# mini_pcie.net
KiCad netlist of a schematic drawn in Altium Designer
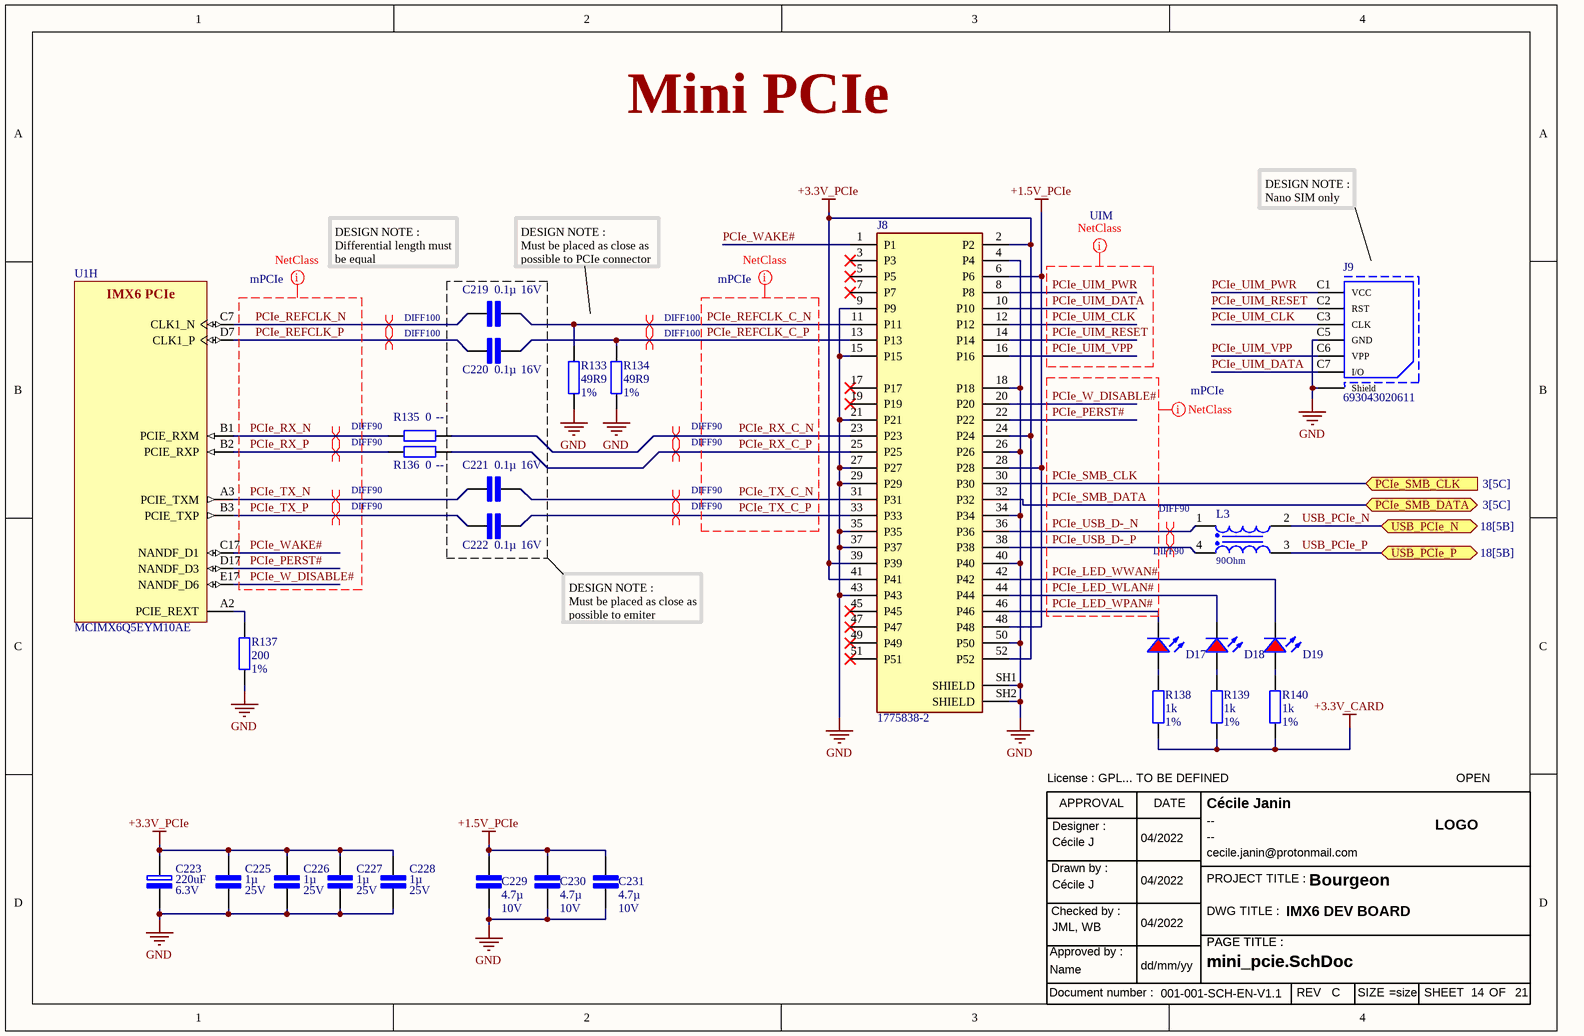
[diagram p0: mini_pcie.SchDoc]

(export (version "E")
  (design (tool "Eeschema 10.0.6"))
  (components
    (comp (ref "C219")
      (value "0.1µ")
      (footprint "Cap cer 0402/1005")
      (description "cap solid electrolyte 0.1µ 6.3V 10%")
      (fields (field (name "TENSION DU DIÉLECTRIQUE") "16V"))
      (libsource (lib "First Board IMX6") (part "cap 0.1µ 16V"))
    )
    (comp (ref "C220")
      (value "0.1µ")
      (footprint "Cap cer 0402/1005")
      (description "cap solid electrolyte 0.1µ 6.3V 10%")
      (fields (field (name "TENSION DU DIÉLECTRIQUE") "16V"))
      (libsource (lib "First Board IMX6") (part "cap 0.1µ 16V"))
    )
    (comp (ref "C221")
      (value "0.1µ")
      (footprint "Cap cer 0402/1005")
      (description "cap solid electrolyte 0.1µ 6.3V 10%")
      (fields (field (name "TENSION DU DIÉLECTRIQUE") "16V"))
      (libsource (lib "First Board IMX6") (part "cap 0.1µ 16V"))
    )
    (comp (ref "C222")
      (value "0.1µ")
      (footprint "Cap cer 0402/1005")
      (description "cap solid electrolyte 0.1µ 6.3V 10%")
      (fields (field (name "TENSION DU DIÉLECTRIQUE") "16V"))
      (libsource (lib "First Board IMX6") (part "cap 0.1µ 16V"))
    )
    (comp (ref "C223")
      (value "220uF")
      (footprint "cap polymer wurth")
      (description "WCAP-PHGP Aluminum Polymer Capacitor, H-Chip SMT, L7.3W4.3H1.9mm, 220uF, 6.3V 875015119006")
      (fields
        (field (name "MANUFACTURER") "Wurth Elektronik")
        (field (name "MANUFACTURER PART NUMBER") "875015119006")
        (field (name "RATED VOLTAGE (DC)") "6.3V")
      )
      (libsource (lib "First Board IMX6") (part "cap 220µ 6.3V"))
    )
    (comp (ref "C225")
      (value "1µ")
      (footprint "Cap cer 0402/1005")
      (description "cap cer 1µ 25V 10% X5R 0402")
      (fields (field (name "TENSION DU DIÉLECTRIQUE") "25V"))
      (libsource (lib "First Board IMX6") (part "cap 1µ 25V"))
    )
    (comp (ref "C226")
      (value "1µ")
      (footprint "Cap cer 0402/1005")
      (description "cap cer 1µ 25V 10% X5R 0402")
      (fields (field (name "TENSION DU DIÉLECTRIQUE") "25V"))
      (libsource (lib "First Board IMX6") (part "cap 1µ 25V"))
    )
    (comp (ref "C227")
      (value "1µ")
      (footprint "Cap cer 0402/1005")
      (description "cap cer 1µ 25V 10% X5R 0402")
      (fields (field (name "TENSION DU DIÉLECTRIQUE") "25V"))
      (libsource (lib "First Board IMX6") (part "cap 1µ 25V"))
    )
    (comp (ref "C228")
      (value "1µ")
      (footprint "Cap cer 0402/1005")
      (description "cap cer 1µ 25V 10% X5R 0402")
      (fields (field (name "TENSION DU DIÉLECTRIQUE") "25V"))
      (libsource (lib "First Board IMX6") (part "cap 1µ 25V"))
    )
    (comp (ref "C229")
      (value "4.7µ")
      (footprint "Cap cer 0402/1005")
      (description "cap cer 4.7µ 10V 10% X7R 0402")
      (fields (field (name "TENSION DU DIÉLECTRIQUE") "10V"))
      (libsource (lib "First Board IMX6") (part "cap 4.7µ 10V"))
    )
    (comp (ref "C230")
      (value "4.7µ")
      (footprint "Cap cer 0402/1005")
      (description "cap cer 4.7µ 10V 10% X7R 0402")
      (fields (field (name "TENSION DU DIÉLECTRIQUE") "10V"))
      (libsource (lib "First Board IMX6") (part "cap 4.7µ 10V"))
    )
    (comp (ref "C231")
      (value "4.7µ")
      (footprint "Cap cer 0402/1005")
      (description "cap cer 4.7µ 10V 10% X7R 0402")
      (fields (field (name "TENSION DU DIÉLECTRIQUE") "10V"))
      (libsource (lib "First Board IMX6") (part "cap 4.7µ 10V"))
    )
    (comp (ref "D17")
      (value "Red, 2V, 120deg")
      (footprint "LED red 0603")
      (description "WL-SMCC SMD Mono-color Chip LED Compact, size 0603, Red, 2V, 120deg 150060RS73220")
      (fields (field (name "PART NUMBER") "150060RS73220") (field (name "PUBLISHER") "Wurth Elektronik"))
      (libsource (lib "First Board IMX6") (part "LED Red 0603"))
    )
    (comp (ref "D18")
      (value "Red, 2V, 120deg")
      (footprint "LED red 0603")
      (description "WL-SMCC SMD Mono-color Chip LED Compact, size 0603, Red, 2V, 120deg 150060RS73220")
      (fields (field (name "PART NUMBER") "150060RS73220") (field (name "PUBLISHER") "Wurth Elektronik"))
      (libsource (lib "First Board IMX6") (part "LED Red 0603"))
    )
    (comp (ref "D19")
      (value "Red, 2V, 120deg")
      (footprint "LED red 0603")
      (description "WL-SMCC SMD Mono-color Chip LED Compact, size 0603, Red, 2V, 120deg 150060RS73220")
      (fields (field (name "PART NUMBER") "150060RS73220") (field (name "PUBLISHER") "Wurth Elektronik"))
      (libsource (lib "First Board IMX6") (part "LED Red 0603"))
    )
    (comp (ref "J8")
      (value "1775838-2")
      (footprint "mini_PCIe_1775838-2")
      (description "mini pcie connector")
      (libsource (lib "First Board IMX6") (part "mini_PCIe_1775838-2"))
    )
    (comp (ref "J9")
      (value "693043020611")
      (footprint "nano SIM 693043020611")
      (libsource (lib "First Board IMX6") (part "Nano SIM"))
    )
    (comp (ref "L3")
      (value "90Ohm")
      (footprint "inductor coupled usb 0603")
      (description "WE-CNSW SMT Common Mode Line Filter, size 0603, 90Ohm, 0.55A, 50V")
      (fields
        (field (name "MANUFACTURER PART NUMBER") "744230900")
        (field (name "MANUFACTURER") "Wurth Elektronik")
      )
      (libsource (lib "First Board IMX6") (part "inductor coupled USB"))
    )
    (comp (ref "R133")
      (value "49R9")
      (footprint "Res 0402/1005")
      (description "res 49R9 ohm 1% 0402")
      (fields (field (name "POURCENTAGE") "1%"))
      (libsource (lib "First Board IMX6") (part "res 49R9 1%"))
    )
    (comp (ref "R134")
      (value "49R9")
      (footprint "Res 0402/1005")
      (description "res 49R9 ohm 1% 0402")
      (fields (field (name "POURCENTAGE") "1%"))
      (libsource (lib "First Board IMX6") (part "res 49R9 1%"))
    )
    (comp (ref "R135")
      (value "0")
      (footprint "Res 0402/1005")
      (description "res 0402")
      (fields (field (name "POURCENTAGE") "--"))
      (libsource (lib "First Board IMX6") (part "res 0Ohm small"))
    )
    (comp (ref "R136")
      (value "0")
      (footprint "Res 0402/1005")
      (description "res 0402")
      (fields (field (name "POURCENTAGE") "--"))
      (libsource (lib "First Board IMX6") (part "res 0Ohm small"))
    )
    (comp (ref "R137")
      (value "200")
      (footprint "Res 0402/1005")
      (description "res 200 1% 0402")
      (fields (field (name "POURCENTAGE") "1%"))
      (libsource (lib "First Board IMX6") (part "res 200 1%"))
    )
    (comp (ref "R138")
      (value "1k")
      (footprint "Res 0402/1005")
      (description "res 1k 1% 0402")
      (fields (field (name "POURCENTAGE") "1%"))
      (libsource (lib "First Board IMX6") (part "res 1k 1%"))
    )
    (comp (ref "R139")
      (value "1k")
      (footprint "Res 0402/1005")
      (description "res 1k 1% 0402")
      (fields (field (name "POURCENTAGE") "1%"))
      (libsource (lib "First Board IMX6") (part "res 1k 1%"))
    )
    (comp (ref "R140")
      (value "1k")
      (footprint "Res 0402/1005")
      (description "res 1k 1% 0402")
      (fields (field (name "POURCENTAGE") "1%"))
      (libsource (lib "First Board IMX6") (part "res 1k 1%"))
    )
    (comp (ref "TB13")
      (value "Title bloc ANSI modified")
      (libsource (lib "First Board IMX6") (part "Title bloc ANSI"))
    )
    (comp (ref "U1")
      (value "MCIMX6Q5EYM10AE")
      (footprint "FRES-2197-01")
      (fields
        (field (name "PARTNUMBER") "MCIMX6Q5EYM10ACR")
        (field (name "MANUFACTURER") "Freescale Semiconductor")
      )
      (libsource (lib "First Board IMX6") (part "IMX6Q5EYM10AE"))
    )
  )
  (nets
    (net (code "1") (name "+1.5V_PCIe") (class "Default")
      (node (ref "C229") (pin "1") (pinfunction "3_1") (pintype "passive"))
      (node (ref "C230") (pin "1") (pinfunction "3_1") (pintype "passive"))
      (node (ref "C231") (pin "1") (pinfunction "3_1") (pintype "passive"))
      (node (ref "J8") (pin "28") (pinfunction "P28_28") (pintype "passive"))
      (node (ref "J8") (pin "48") (pinfunction "P48_48") (pintype "passive"))
      (node (ref "J8") (pin "6") (pinfunction "P6_6") (pintype "passive"))
    )
    (net (code "2") (name "+3.3V_CARD") (class "Default")
      (node (ref "R138") (pin "1") (pintype "passive"))
      (node (ref "R139") (pin "1") (pintype "passive"))
      (node (ref "R140") (pin "1") (pintype "passive"))
    )
    (net (code "3") (name "+3.3V_PCIe") (class "Default")
      (node (ref "C223") (pin "1") (pinfunction "P_1") (pintype "passive"))
      (node (ref "C225") (pin "1") (pinfunction "3_1") (pintype "passive"))
      (node (ref "C226") (pin "1") (pinfunction "3_1") (pintype "passive"))
      (node (ref "C227") (pin "1") (pinfunction "3_1") (pintype "passive"))
      (node (ref "C228") (pin "1") (pinfunction "3_1") (pintype "passive"))
      (node (ref "J8") (pin "2") (pinfunction "P2_2") (pintype "passive"))
      (node (ref "J8") (pin "24") (pinfunction "P24_24") (pintype "passive"))
      (node (ref "J8") (pin "39") (pinfunction "P39_39") (pintype "passive"))
      (node (ref "J8") (pin "41") (pinfunction "P41_41") (pintype "passive"))
      (node (ref "J8") (pin "52") (pinfunction "P52_52") (pintype "passive"))
    )
    (net (code "4") (name "/PCIe_LED_WLAN#") (class "Default")
      (node (ref "D18") (pin "1") (pinfunction "K_1") (pintype "passive"))
      (node (ref "J8") (pin "44") (pinfunction "P44_44") (pintype "passive"))
    )
    (net (code "5") (name "/PCIe_LED_WPAN#") (class "Default")
      (node (ref "D17") (pin "1") (pinfunction "K_1") (pintype "passive"))
      (node (ref "J8") (pin "46") (pinfunction "P46_46") (pintype "passive"))
    )
    (net (code "6") (name "/PCIe_LED_WWAN#") (class "Default")
      (node (ref "D19") (pin "1") (pinfunction "K_1") (pintype "passive"))
      (node (ref "J8") (pin "42") (pinfunction "P42_42") (pintype "passive"))
    )
    (net (code "7") (name "/PCIe_PERST#") (class "Default")
      (node (ref "J8") (pin "22") (pinfunction "P22_22") (pintype "passive"))
      (node (ref "U1") (pin "D17") (pinfunction "NANDF_D3_D17") (pintype "bidirectional"))
    )
    (net (code "8") (name "/PCIe_REFCLK_C_N") (class "Default")
      (node (ref "C219") (pin "2") (pinfunction "4_2") (pintype "passive"))
      (node (ref "J8") (pin "11") (pinfunction "P11_11") (pintype "passive"))
      (node (ref "R133") (pin "2") (pintype "passive"))
    )
    (net (code "9") (name "/PCIe_REFCLK_C_P") (class "Default")
      (node (ref "C220") (pin "2") (pinfunction "4_2") (pintype "passive"))
      (node (ref "J8") (pin "13") (pinfunction "P13_13") (pintype "passive"))
      (node (ref "R134") (pin "2") (pintype "passive"))
    )
    (net (code "10") (name "/PCIe_REFCLK_N") (class "Default")
      (node (ref "C219") (pin "1") (pinfunction "3_1") (pintype "passive"))
      (node (ref "U1") (pin "C7") (pinfunction "CLK1_N_C7") (pintype "bidirectional"))
    )
    (net (code "11") (name "/PCIe_REFCLK_P") (class "Default")
      (node (ref "C220") (pin "1") (pinfunction "3_1") (pintype "passive"))
      (node (ref "U1") (pin "D7") (pinfunction "CLK1_P_D7") (pintype "bidirectional"))
    )
    (net (code "12") (name "/PCIe_RX_C_N") (class "Default")
      (node (ref "J8") (pin "23") (pinfunction "P23_23") (pintype "passive"))
      (node (ref "R135") (pin "2") (pintype "passive"))
    )
    (net (code "13") (name "/PCIe_RX_C_P") (class "Default")
      (node (ref "J8") (pin "25") (pinfunction "P25_25") (pintype "passive"))
      (node (ref "R136") (pin "2") (pintype "passive"))
    )
    (net (code "14") (name "/PCIe_RX_N") (class "Default")
      (node (ref "R135") (pin "1") (pintype "passive"))
      (node (ref "U1") (pin "B1") (pinfunction "PCIE_RXM_B1") (pintype "input"))
    )
    (net (code "15") (name "/PCIe_RX_P") (class "Default")
      (node (ref "R136") (pin "1") (pintype "passive"))
      (node (ref "U1") (pin "B2") (pinfunction "PCIE_RXP_B2") (pintype "input"))
    )
    (net (code "16") (name "/PCIe_SMB_CLK") (class "Default")
      (node (ref "J8") (pin "30") (pinfunction "P30_30") (pintype "passive"))
    )
    (net (code "17") (name "/PCIe_SMB_DATA") (class "Default")
      (node (ref "J8") (pin "32") (pinfunction "P32_32") (pintype "passive"))
    )
    (net (code "18") (name "/PCIe_TX_C_N") (class "Default")
      (node (ref "C221") (pin "2") (pinfunction "4_2") (pintype "passive"))
      (node (ref "J8") (pin "31") (pinfunction "P31_31") (pintype "passive"))
    )
    (net (code "19") (name "/PCIe_TX_C_P") (class "Default")
      (node (ref "C222") (pin "2") (pinfunction "4_2") (pintype "passive"))
      (node (ref "J8") (pin "33") (pinfunction "P33_33") (pintype "passive"))
    )
    (net (code "20") (name "/PCIe_TX_N") (class "Default")
      (node (ref "C221") (pin "1") (pinfunction "3_1") (pintype "passive"))
      (node (ref "U1") (pin "A3") (pinfunction "PCIE_TXM_A3") (pintype "output"))
    )
    (net (code "21") (name "/PCIe_TX_P") (class "Default")
      (node (ref "C222") (pin "1") (pinfunction "3_1") (pintype "passive"))
      (node (ref "U1") (pin "B3") (pinfunction "PCIE_TXP_B3") (pintype "output"))
    )
    (net (code "22") (name "/PCIe_UIM_CLK") (class "Default")
      (node (ref "J8") (pin "12") (pinfunction "P12_12") (pintype "passive"))
      (node (ref "J9") (pin "C3") (pinfunction "CLK_C3") (pintype "passive"))
    )
    (net (code "23") (name "/PCIe_UIM_DATA") (class "Default")
      (node (ref "J8") (pin "10") (pinfunction "P10_10") (pintype "passive"))
      (node (ref "J9") (pin "C7") (pinfunction "I/O_C7") (pintype "passive"))
    )
    (net (code "24") (name "/PCIe_UIM_PWR") (class "Default")
      (node (ref "J8") (pin "8") (pinfunction "P8_8") (pintype "passive"))
      (node (ref "J9") (pin "C1") (pinfunction "VCC_C1") (pintype "passive"))
    )
    (net (code "25") (name "/PCIe_UIM_RESET") (class "Default")
      (node (ref "J8") (pin "14") (pinfunction "P14_14") (pintype "passive"))
      (node (ref "J9") (pin "C2") (pinfunction "RST_C2") (pintype "passive"))
    )
    (net (code "26") (name "/PCIe_UIM_VPP") (class "Default")
      (node (ref "J8") (pin "16") (pinfunction "P16_16") (pintype "passive"))
      (node (ref "J9") (pin "C6") (pinfunction "VPP_C6") (pintype "passive"))
    )
    (net (code "27") (name "/PCIe_USB_D-_N") (class "Default")
      (node (ref "J8") (pin "36") (pinfunction "P36_36") (pintype "passive"))
      (node (ref "L3") (pin "1") (pinfunction "1_1") (pintype "passive"))
    )
    (net (code "28") (name "/PCIe_USB_D-_P") (class "Default")
      (node (ref "J8") (pin "38") (pinfunction "P38_38") (pintype "passive"))
      (node (ref "L3") (pin "4") (pinfunction "4_4") (pintype "passive"))
    )
    (net (code "29") (name "/PCIe_WAKE#") (class "Default")
      (node (ref "J8") (pin "1") (pinfunction "P1_1") (pintype "passive"))
      (node (ref "U1") (pin "C17") (pinfunction "NANDF_D1_C17") (pintype "bidirectional"))
    )
    (net (code "30") (name "/PCIe_W_DISABLE#") (class "Default")
      (node (ref "J8") (pin "20") (pinfunction "P20_20") (pintype "passive"))
      (node (ref "U1") (pin "E17") (pinfunction "NANDF_D6_E17") (pintype "bidirectional"))
    )
    (net (code "31") (name "/USB_PCIe_N") (class "Default")
      (node (ref "L3") (pin "2") (pinfunction "2_2") (pintype "passive"))
    )
    (net (code "32") (name "/USB_PCIe_P") (class "Default")
      (node (ref "L3") (pin "3") (pinfunction "3_3") (pintype "passive"))
    )
    (net (code "33") (name "GND") (class "Default")
      (node (ref "C223") (pin "2") (pinfunction "N_2") (pintype "passive"))
      (node (ref "C225") (pin "2") (pinfunction "4_2") (pintype "passive"))
      (node (ref "C226") (pin "2") (pinfunction "4_2") (pintype "passive"))
      (node (ref "C227") (pin "2") (pinfunction "4_2") (pintype "passive"))
      (node (ref "C228") (pin "2") (pinfunction "4_2") (pintype "passive"))
      (node (ref "C229") (pin "2") (pinfunction "4_2") (pintype "passive"))
      (node (ref "C230") (pin "2") (pinfunction "4_2") (pintype "passive"))
      (node (ref "C231") (pin "2") (pinfunction "4_2") (pintype "passive"))
      (node (ref "J8") (pin "15") (pinfunction "P15_15") (pintype "passive"))
      (node (ref "J8") (pin "18") (pinfunction "P18_18") (pintype "passive"))
      (node (ref "J8") (pin "21") (pinfunction "P21_21") (pintype "passive"))
      (node (ref "J8") (pin "26") (pinfunction "P26_26") (pintype "passive"))
      (node (ref "J8") (pin "27") (pinfunction "P27_27") (pintype "passive"))
      (node (ref "J8") (pin "29") (pinfunction "P29_29") (pintype "passive"))
      (node (ref "J8") (pin "34") (pinfunction "P34_34") (pintype "passive"))
      (node (ref "J8") (pin "35") (pinfunction "P35_35") (pintype "passive"))
      (node (ref "J8") (pin "37") (pinfunction "P37_37") (pintype "passive"))
      (node (ref "J8") (pin "4") (pinfunction "P4_4") (pintype "passive"))
      (node (ref "J8") (pin "40") (pinfunction "P40_40") (pintype "passive"))
      (node (ref "J8") (pin "43") (pinfunction "P43_43") (pintype "passive"))
      (node (ref "J8") (pin "50") (pinfunction "P50_50") (pintype "passive"))
      (node (ref "J8") (pin "9") (pinfunction "P9_9") (pintype "passive"))
      (node (ref "J8") (pin "SH1") (pinfunction "SHIELD_SH1") (pintype "passive"))
      (node (ref "J8") (pin "SH2") (pinfunction "SHIELD_SH2") (pintype "passive"))
      (node (ref "J9") (pin "C5") (pinfunction "GND_C5") (pintype "passive"))
      (node (ref "J9") (pin "Shield") (pinfunction "Shield_Shield") (pintype "passive"))
      (node (ref "R133") (pin "1") (pintype "passive"))
      (node (ref "R134") (pin "1") (pintype "passive"))
      (node (ref "R137") (pin "1") (pintype "passive"))
    )
    (net (code "34") (name "Net-(D17-A)") (class "Default")
      (node (ref "D17") (pin "2") (pinfunction "A_2") (pintype "passive"))
      (node (ref "R138") (pin "2") (pintype "passive"))
    )
    (net (code "35") (name "Net-(D18-A)") (class "Default")
      (node (ref "D18") (pin "2") (pinfunction "A_2") (pintype "passive"))
      (node (ref "R139") (pin "2") (pintype "passive"))
    )
    (net (code "36") (name "Net-(D19-A)") (class "Default")
      (node (ref "D19") (pin "2") (pinfunction "A_2") (pintype "passive"))
      (node (ref "R140") (pin "2") (pintype "passive"))
    )
    (net (code "37") (name "Net-(U1H-PCIE_REXT)") (class "Default")
      (node (ref "R137") (pin "2") (pintype "passive"))
      (node (ref "U1") (pin "A2") (pinfunction "PCIE_REXT_A2") (pintype "passive"))
    )
    (net (code "38") (name "unconnected-(J8-P3-Pad3)") (class "Default")
      (node (ref "J8") (pin "3") (pinfunction "P3_3") (pintype "passive+no_connect"))
    )
    (net (code "39") (name "unconnected-(J8-P5-Pad5)") (class "Default")
      (node (ref "J8") (pin "5") (pinfunction "P5_5") (pintype "passive+no_connect"))
    )
    (net (code "40") (name "unconnected-(J8-P7-Pad7)") (class "Default")
      (node (ref "J8") (pin "7") (pinfunction "P7_7") (pintype "passive+no_connect"))
    )
    (net (code "41") (name "unconnected-(J8-P17-Pad17)") (class "Default")
      (node (ref "J8") (pin "17") (pinfunction "P17_17") (pintype "passive+no_connect"))
    )
    (net (code "42") (name "unconnected-(J8-P19-Pad19)") (class "Default")
      (node (ref "J8") (pin "19") (pinfunction "P19_19") (pintype "passive+no_connect"))
    )
    (net (code "43") (name "unconnected-(J8-P45-Pad45)") (class "Default")
      (node (ref "J8") (pin "45") (pinfunction "P45_45") (pintype "passive+no_connect"))
    )
    (net (code "44") (name "unconnected-(J8-P47-Pad47)") (class "Default")
      (node (ref "J8") (pin "47") (pinfunction "P47_47") (pintype "passive+no_connect"))
    )
    (net (code "45") (name "unconnected-(J8-P49-Pad49)") (class "Default")
      (node (ref "J8") (pin "49") (pinfunction "P49_49") (pintype "passive+no_connect"))
    )
    (net (code "46") (name "unconnected-(J8-P51-Pad51)") (class "Default")
      (node (ref "J8") (pin "51") (pinfunction "P51_51") (pintype "passive+no_connect"))
    )
  )
)
